# Toberemoved_Principal.net
KiCad netlist of a schematic drawn in Altium Designer
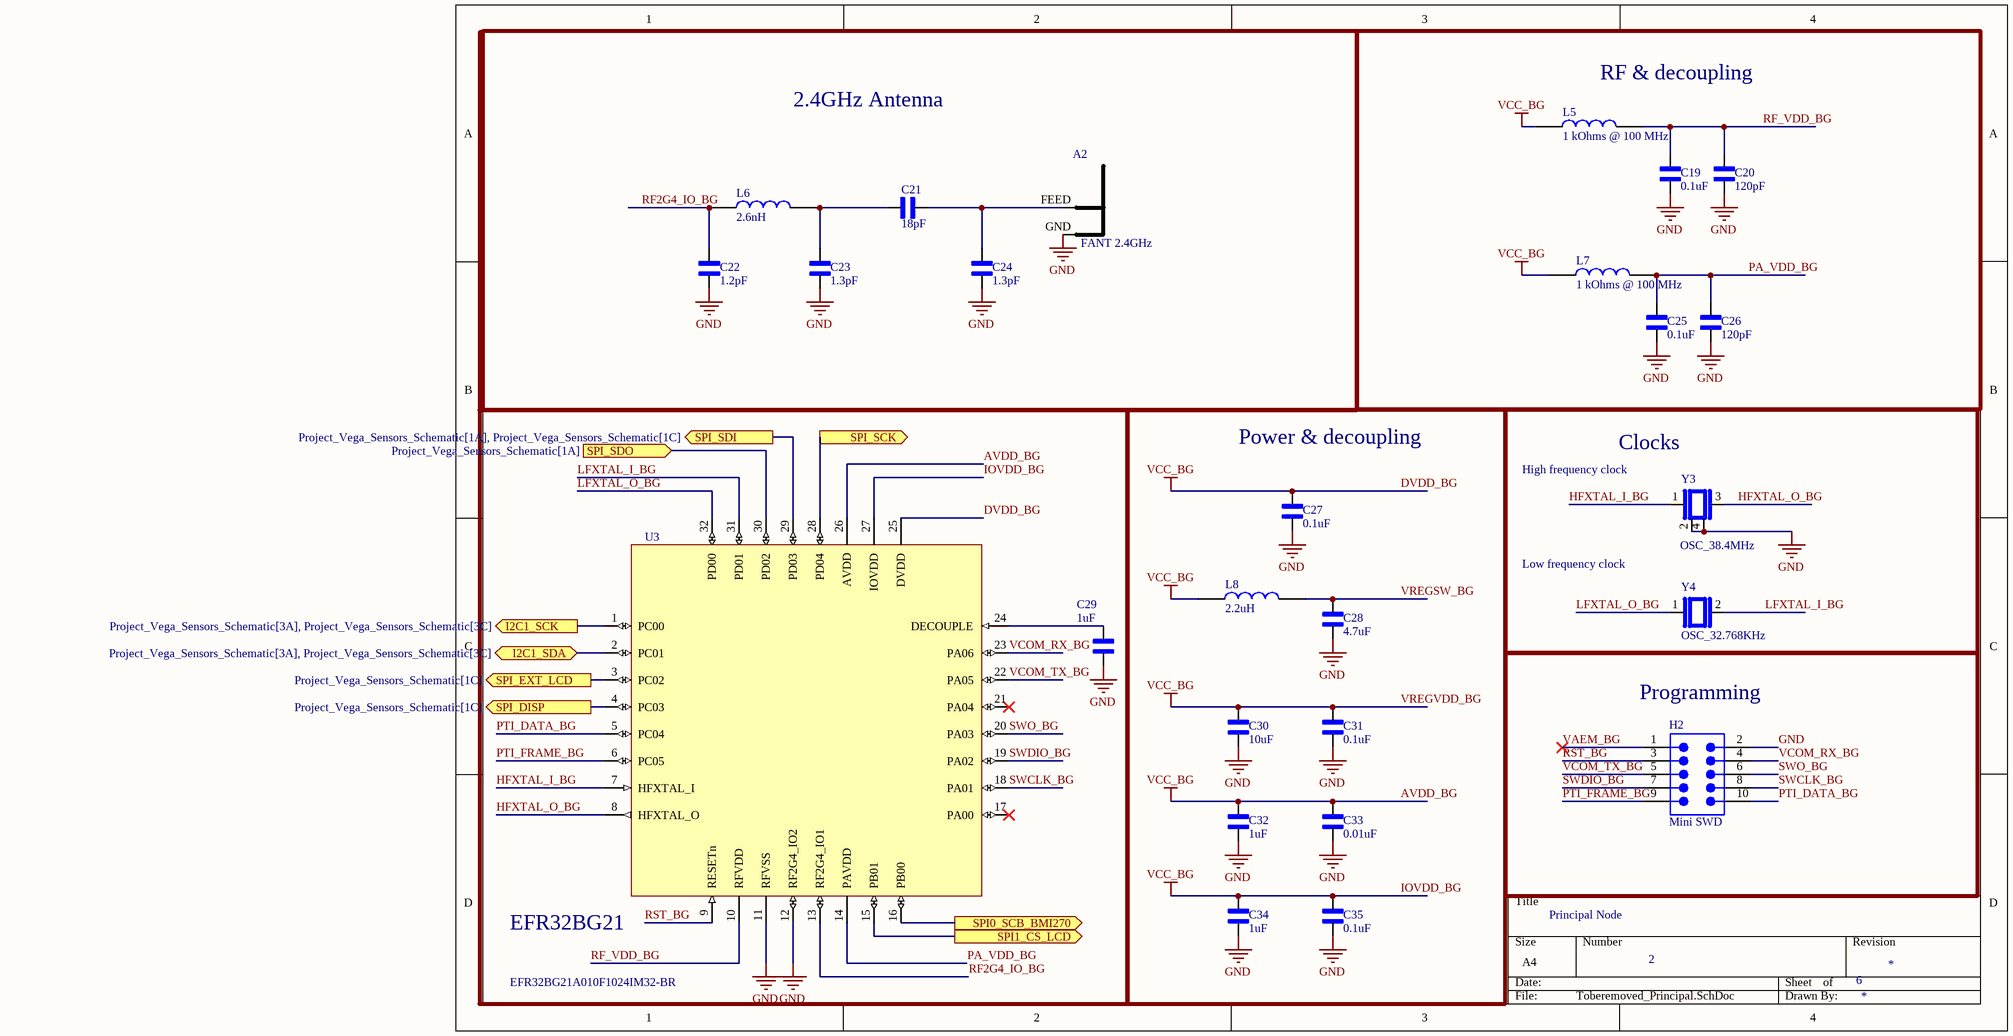
[diagram p0: Toberemoved_Principal.SchDoc]

(export (version "E")
  (design (tool "Eeschema 10.0.6"))
  (components
    (comp (ref "A2")
      (value "FANT 2.4GHz")
      (footprint "FANT_2P4")
      (description "Inverted F antenna")
      (libsource (lib "Project_Vega") (part "FANT_2P4"))
    )
    (comp (ref "C19")
      (value "0.1uF")
      (footprint "CAPC1608X90")
      (description "0.1 ÂµF Â±10% 50V Ceramic Capacitor X7R 0603 (1608 Metric)")
      (fields (field (name "MF") "Yageo") (field (name "MP") "CC0603KRX7R9BB104"))
      (libsource (lib "Project_Vega") (part "CC0603KRX7R9BB104"))
    )
    (comp (ref "C20")
      (value "120pF")
      (footprint "CAPC1608X90")
      (description "0.1 ÂµF Â±10% 50V Ceramic Capacitor X7R 0603 (1608 Metric)")
      (fields (field (name "MF") "Yageo") (field (name "MP") "CC0603KRX7R9BB104"))
      (libsource (lib "Project_Vega") (part "CC0603KRX7R9BB104"))
    )
    (comp (ref "C21")
      (value "18pF")
      (footprint "CAPC1608X90")
      (description "0.1 ÂµF Â±10% 50V Ceramic Capacitor X7R 0603 (1608 Metric)")
      (fields (field (name "MF") "Yageo") (field (name "MP") "CC0603KRX7R9BB104"))
      (libsource (lib "") (part "CC0603KRX7R9BB104_1"))
    )
    (comp (ref "C22")
      (value "1.2pF")
      (footprint "CAPC1608X90")
      (description "0.1 ÂµF Â±10% 50V Ceramic Capacitor X7R 0603 (1608 Metric)")
      (fields (field (name "MF") "Yageo") (field (name "MP") "CC0603KRX7R9BB104"))
      (libsource (lib "Project_Vega") (part "CC0603KRX7R9BB104"))
    )
    (comp (ref "C23")
      (value "1.3pF")
      (footprint "CAPC1608X90")
      (description "0.1 ÂµF Â±10% 50V Ceramic Capacitor X7R 0603 (1608 Metric)")
      (fields (field (name "MF") "Yageo") (field (name "MP") "CC0603KRX7R9BB104"))
      (libsource (lib "Project_Vega") (part "CC0603KRX7R9BB104"))
    )
    (comp (ref "C24")
      (value "1.3pF")
      (footprint "CAPC1608X90")
      (description "0.1 ÂµF Â±10% 50V Ceramic Capacitor X7R 0603 (1608 Metric)")
      (fields (field (name "MF") "Yageo") (field (name "MP") "CC0603KRX7R9BB104"))
      (libsource (lib "Project_Vega") (part "CC0603KRX7R9BB104"))
    )
    (comp (ref "C25")
      (value "0.1uF")
      (footprint "CAPC1608X90")
      (description "0.1 ÂµF Â±10% 50V Ceramic Capacitor X7R 0603 (1608 Metric)")
      (fields (field (name "MF") "Yageo") (field (name "MP") "CC0603KRX7R9BB104"))
      (libsource (lib "Project_Vega") (part "CC0603KRX7R9BB104"))
    )
    (comp (ref "C26")
      (value "120pF")
      (footprint "CAPC1608X90")
      (description "0.1 ÂµF Â±10% 50V Ceramic Capacitor X7R 0603 (1608 Metric)")
      (fields (field (name "MF") "Yageo") (field (name "MP") "CC0603KRX7R9BB104"))
      (libsource (lib "Project_Vega") (part "CC0603KRX7R9BB104"))
    )
    (comp (ref "C27")
      (value "0.1uF")
      (footprint "CAPC1608X90")
      (description "0.1 ÂµF Â±10% 50V Ceramic Capacitor X7R 0603 (1608 Metric)")
      (fields (field (name "MF") "Yageo") (field (name "MP") "CC0603KRX7R9BB104"))
      (libsource (lib "Project_Vega") (part "CC0603KRX7R9BB104"))
    )
    (comp (ref "C28")
      (value "4.7uF")
      (footprint "CAPC1608X90")
      (description "0.1 ÂµF Â±10% 50V Ceramic Capacitor X7R 0603 (1608 Metric)")
      (fields (field (name "MF") "Yageo") (field (name "MP") "CC0603KRX7R9BB104"))
      (libsource (lib "Project_Vega") (part "CC0603KRX7R9BB104"))
    )
    (comp (ref "C29")
      (value "1uF")
      (footprint "CAPC1608X90")
      (description "0.1 ÂµF Â±10% 50V Ceramic Capacitor X7R 0603 (1608 Metric)")
      (fields (field (name "MF") "Yageo") (field (name "MP") "CC0603KRX7R9BB104"))
      (libsource (lib "Project_Vega") (part "CC0603KRX7R9BB104"))
    )
    (comp (ref "C30")
      (value "10uF")
      (footprint "CAPC1608X90")
      (description "0.1 ÂµF Â±10% 50V Ceramic Capacitor X7R 0603 (1608 Metric)")
      (fields (field (name "MF") "Yageo") (field (name "MP") "CC0603KRX7R9BB104"))
      (libsource (lib "Project_Vega") (part "CC0603KRX7R9BB104"))
    )
    (comp (ref "C31")
      (value "0.1uF")
      (footprint "CAPC1608X90")
      (description "0.1 ÂµF Â±10% 50V Ceramic Capacitor X7R 0603 (1608 Metric)")
      (fields (field (name "MF") "Yageo") (field (name "MP") "CC0603KRX7R9BB104"))
      (libsource (lib "Project_Vega") (part "CC0603KRX7R9BB104"))
    )
    (comp (ref "C32")
      (value "1uF")
      (footprint "CAPC1608X90")
      (description "0.1 ÂµF Â±10% 50V Ceramic Capacitor X7R 0603 (1608 Metric)")
      (fields (field (name "MF") "Yageo") (field (name "MP") "CC0603KRX7R9BB104"))
      (libsource (lib "Project_Vega") (part "CC0603KRX7R9BB104"))
    )
    (comp (ref "C33")
      (value "0.01uF")
      (footprint "CAPC1608X90")
      (description "0.1 ÂµF Â±10% 50V Ceramic Capacitor X7R 0603 (1608 Metric)")
      (fields (field (name "MF") "Yageo") (field (name "MP") "CC0603KRX7R9BB104"))
      (libsource (lib "Project_Vega") (part "CC0603KRX7R9BB104"))
    )
    (comp (ref "C34")
      (value "1uF")
      (footprint "CAPC1608X90")
      (description "0.1 ÂµF Â±10% 50V Ceramic Capacitor X7R 0603 (1608 Metric)")
      (fields (field (name "MF") "Yageo") (field (name "MP") "CC0603KRX7R9BB104"))
      (libsource (lib "Project_Vega") (part "CC0603KRX7R9BB104"))
    )
    (comp (ref "C35")
      (value "0.1uF")
      (footprint "CAPC1608X90")
      (description "0.1 ÂµF Â±10% 50V Ceramic Capacitor X7R 0603 (1608 Metric)")
      (fields (field (name "MF") "Yageo") (field (name "MP") "CC0603KRX7R9BB104"))
      (libsource (lib "Project_Vega") (part "CC0603KRX7R9BB104"))
    )
    (comp (ref "H2")
      (value "Mini SWD")
      (footprint "FTSH-105-01-XXX-DV-K")
      (description "Mini SWD 0.05\" Pitch Connector - 10 Pin SMT Box Header")
      (fields
        (field (name "MANUFACTURER") "Adafruit Industries")
        (field (name "MANUFACTURER PART NUMBER") "4048")
      )
      (libsource (lib "Connectors") (part "Debug Connector Mini SWD - 0.05{dblquote}"))
    )
    (comp (ref "L5")
      (value "1 kOhms @ 100 MHz")
      (footprint "INDC1608X95N")
      (description "Inductor with Inductance 10uH Tol.+/-20% Package 0603 (1608)")
      (fields (field (name "MP") "LQM18DN100M70L") (field (name "MF") "Murata Electronics"))
      (libsource (lib "Project_Vega") (part "LQM18DN100M70L"))
    )
    (comp (ref "L6")
      (value "2.6nH")
      (footprint "INDC1608X95N")
      (description "Inductor with Inductance 10uH Tol.+/-20% Package 0603 (1608)")
      (fields (field (name "MP") "LQM18DN100M70L") (field (name "MF") "Murata Electronics"))
      (libsource (lib "Project_Vega") (part "LQM18DN100M70L"))
    )
    (comp (ref "L7")
      (value "1 kOhms @ 100 MHz")
      (footprint "INDC1608X95N")
      (description "Inductor with Inductance 10uH Tol.+/-20% Package 0603 (1608)")
      (fields (field (name "MP") "LQM18DN100M70L") (field (name "MF") "Murata Electronics"))
      (libsource (lib "Project_Vega") (part "LQM18DN100M70L"))
    )
    (comp (ref "L8")
      (value "2.2uH")
      (footprint "INDC1608X95N")
      (description "Inductor with Inductance 10uH Tol.+/-20% Package 0603 (1608)")
      (fields (field (name "MP") "LQM18DN100M70L") (field (name "MF") "Murata Electronics"))
      (libsource (lib "Project_Vega") (part "LQM18DN100M70L"))
    )
    (comp (ref "U3")
      (value "EFR32BG21A010F1024IM32-BR")
      (footprint "QFN32-EFR32xG2xIM32-BR")
      (description "Blue Gecko, QFN32, 2.4G, 10dB, Bluetooth 5.1, 1024kB, 96kB(RAM), 20 GPIO")
      (fields (field (name "MANUFACTURER") "Silicon Labs"))
      (libsource (lib "Project_Vega") (part "EFR32BG21A010F1024IM32-BR"))
    )
    (comp (ref "Y3")
      (value "OSC_38.4MHz")
      (footprint "OSC_38.4MHz")
      (description "38.4 MHz ±10ppm Crystal 10pF 40 Ohms 4-SMD, No Lead")
      (fields
        (field (name "MF") "{'manufacturer': u'Murata Electronics'}")
        (field (name "MP") "XRCGB38M400F2P00R0")
      )
      (libsource (lib "Project_Vega") (part "OSC_38.4MHz"))
    )
    (comp (ref "Y4")
      (value "OSC_32.768KHz")
      (footprint "OSC_32.768KHz")
      (description "Tuning Fork Crystal 32.768kHz in 1.2 x 2.0mm package")
      (fields (field (name "MF") "Micro Crystal") (field (name "MP") "CM8V-T1A-32.768KHZ-7PF-20PPM-TA-QC"))
      (libsource (lib "Project_Vega") (part "OSC_32.768KHz"))
    )
  )
  (nets
    (net (code "1") (name "/HFXTAL_I_BG") (class "Default")
      (node (ref "U3") (pin "7") (pinfunction "HFXTAL_I_7") (pintype "input"))
      (node (ref "Y3") (pin "1") (pinfunction "1_1") (pintype "passive"))
    )
    (net (code "2") (name "/HFXTAL_O_BG") (class "Default")
      (node (ref "U3") (pin "8") (pinfunction "HFXTAL_O_8") (pintype "output"))
      (node (ref "Y3") (pin "3") (pinfunction "3_3") (pintype "passive"))
    )
    (net (code "3") (name "/I2C1_SCK") (class "Default")
      (node (ref "U3") (pin "1") (pinfunction "PC00_1") (pintype "bidirectional"))
    )
    (net (code "4") (name "/I2C1_SDA") (class "Default")
      (node (ref "U3") (pin "2") (pinfunction "PC01_2") (pintype "bidirectional"))
    )
    (net (code "5") (name "/LFXTAL_I_BG") (class "Default")
      (node (ref "U3") (pin "31") (pinfunction "PD01_31") (pintype "bidirectional"))
      (node (ref "Y4") (pin "2") (pinfunction "2_2") (pintype "passive"))
    )
    (net (code "6") (name "/LFXTAL_O_BG") (class "Default")
      (node (ref "U3") (pin "32") (pinfunction "PD00_32") (pintype "bidirectional"))
      (node (ref "Y4") (pin "1") (pinfunction "1_1") (pintype "passive"))
    )
    (net (code "7") (name "/PA_VDD_BG") (class "Default")
      (node (ref "C25") (pin "1") (pinfunction "1_1") (pintype "passive"))
      (node (ref "C26") (pin "1") (pinfunction "1_1") (pintype "passive"))
      (node (ref "L7") (pin "2") (pinfunction "2_2") (pintype "passive"))
      (node (ref "U3") (pin "14") (pinfunction "PAVDD_14") (pintype "power_in"))
    )
    (net (code "8") (name "/PTI_DATA_BG") (class "Default")
      (node (ref "H2") (pin "10") (pinfunction "10_10") (pintype "passive"))
      (node (ref "U3") (pin "5") (pinfunction "PC04_5") (pintype "bidirectional"))
    )
    (net (code "9") (name "/PTI_FRAME_BG") (class "Default")
      (node (ref "H2") (pin "9") (pinfunction "9_9") (pintype "passive"))
      (node (ref "U3") (pin "6") (pinfunction "PC05_6") (pintype "bidirectional"))
    )
    (net (code "10") (name "/RF2G4_IO_BG") (class "Default")
      (node (ref "C22") (pin "1") (pinfunction "1_1") (pintype "passive"))
      (node (ref "L6") (pin "1") (pinfunction "1_1") (pintype "passive"))
      (node (ref "U3") (pin "13") (pinfunction "RF2G4_IO1_13") (pintype "bidirectional"))
    )
    (net (code "11") (name "/RF_VDD_BG") (class "Default")
      (node (ref "C19") (pin "1") (pinfunction "1_1") (pintype "passive"))
      (node (ref "C20") (pin "1") (pinfunction "1_1") (pintype "passive"))
      (node (ref "L5") (pin "2") (pinfunction "2_2") (pintype "passive"))
      (node (ref "U3") (pin "10") (pinfunction "RFVDD_10") (pintype "power_in"))
    )
    (net (code "12") (name "/RST_BG") (class "Default")
      (node (ref "H2") (pin "3") (pinfunction "3_3") (pintype "passive"))
      (node (ref "U3") (pin "9") (pinfunction "RESETn_9") (pintype "input"))
    )
    (net (code "13") (name "/SPI0_SCB_BMI270") (class "Default")
      (node (ref "U3") (pin "16") (pinfunction "PB00_16") (pintype "bidirectional"))
    )
    (net (code "14") (name "/SPI1_CS_LCD") (class "Default")
      (node (ref "U3") (pin "15") (pinfunction "PB01_15") (pintype "bidirectional"))
    )
    (net (code "15") (name "/SPI_DISP") (class "Default")
      (node (ref "U3") (pin "4") (pinfunction "PC03_4") (pintype "bidirectional"))
    )
    (net (code "16") (name "/SPI_EXT_LCD") (class "Default")
      (node (ref "U3") (pin "3") (pinfunction "PC02_3") (pintype "bidirectional"))
    )
    (net (code "17") (name "/SPI_SCK") (class "Default")
      (node (ref "U3") (pin "28") (pinfunction "PD04_28") (pintype "bidirectional"))
    )
    (net (code "18") (name "/SPI_SDI") (class "Default")
      (node (ref "U3") (pin "29") (pinfunction "PD03_29") (pintype "bidirectional"))
    )
    (net (code "19") (name "/SPI_SDO") (class "Default")
      (node (ref "U3") (pin "30") (pinfunction "PD02_30") (pintype "bidirectional"))
    )
    (net (code "20") (name "/SWCLK_BG") (class "Default")
      (node (ref "H2") (pin "8") (pinfunction "8_8") (pintype "passive"))
      (node (ref "U3") (pin "18") (pinfunction "PA01_18") (pintype "bidirectional"))
    )
    (net (code "21") (name "/SWDIO_BG") (class "Default")
      (node (ref "H2") (pin "7") (pinfunction "7_7") (pintype "passive"))
      (node (ref "U3") (pin "19") (pinfunction "PA02_19") (pintype "bidirectional"))
    )
    (net (code "22") (name "/SWO_BG") (class "Default")
      (node (ref "H2") (pin "6") (pinfunction "6_6") (pintype "passive"))
      (node (ref "U3") (pin "20") (pinfunction "PA03_20") (pintype "bidirectional"))
    )
    (net (code "23") (name "/VAEM_BG") (class "Default")
      (node (ref "H2") (pin "1") (pinfunction "1_1") (pintype "passive+no_connect"))
    )
    (net (code "24") (name "/VCOM_RX_BG") (class "Default")
      (node (ref "H2") (pin "4") (pinfunction "4_4") (pintype "passive"))
      (node (ref "U3") (pin "23") (pinfunction "PA06_23") (pintype "bidirectional"))
    )
    (net (code "25") (name "/VCOM_TX_BG") (class "Default")
      (node (ref "H2") (pin "5") (pinfunction "5_5") (pintype "passive"))
      (node (ref "U3") (pin "22") (pinfunction "PA05_22") (pintype "bidirectional"))
    )
    (net (code "26") (name "/VREGSW_BG") (class "Default")
      (node (ref "C28") (pin "1") (pinfunction "1_1") (pintype "passive"))
      (node (ref "L8") (pin "2") (pinfunction "2_2") (pintype "passive"))
    )
    (net (code "27") (name "GND") (class "Default")
      (node (ref "A2") (pin "GND") (pinfunction "6_GND") (pintype "passive"))
      (node (ref "C19") (pin "2") (pinfunction "2_2") (pintype "passive"))
      (node (ref "C20") (pin "2") (pinfunction "2_2") (pintype "passive"))
      (node (ref "C22") (pin "2") (pinfunction "2_2") (pintype "passive"))
      (node (ref "C23") (pin "2") (pinfunction "2_2") (pintype "passive"))
      (node (ref "C24") (pin "2") (pinfunction "2_2") (pintype "passive"))
      (node (ref "C25") (pin "2") (pinfunction "2_2") (pintype "passive"))
      (node (ref "C26") (pin "2") (pinfunction "2_2") (pintype "passive"))
      (node (ref "C27") (pin "2") (pinfunction "2_2") (pintype "passive"))
      (node (ref "C28") (pin "2") (pinfunction "2_2") (pintype "passive"))
      (node (ref "C29") (pin "2") (pinfunction "2_2") (pintype "passive"))
      (node (ref "C30") (pin "2") (pinfunction "2_2") (pintype "passive"))
      (node (ref "C31") (pin "2") (pinfunction "2_2") (pintype "passive"))
      (node (ref "C32") (pin "2") (pinfunction "2_2") (pintype "passive"))
      (node (ref "C33") (pin "2") (pinfunction "2_2") (pintype "passive"))
      (node (ref "C34") (pin "2") (pinfunction "2_2") (pintype "passive"))
      (node (ref "C35") (pin "2") (pinfunction "2_2") (pintype "passive"))
      (node (ref "H2") (pin "2") (pinfunction "2_2") (pintype "passive"))
      (node (ref "U3") (pin "11") (pinfunction "RFVSS_11") (pintype "power_in"))
      (node (ref "U3") (pin "12") (pinfunction "RF2G4_IO2_12") (pintype "bidirectional"))
      (node (ref "Y3") (pin "2") (pinfunction "2_2") (pintype "passive"))
      (node (ref "Y3") (pin "4") (pinfunction "4_4") (pintype "passive"))
    )
    (net (code "28") (name "Net-(A2-6-PadFEED)") (class "Default")
      (node (ref "A2") (pin "FEED") (pinfunction "6_FEED") (pintype "passive"))
      (node (ref "C21") (pin "2") (pinfunction "2_2") (pintype "passive"))
      (node (ref "C24") (pin "1") (pinfunction "1_1") (pintype "passive"))
    )
    (net (code "29") (name "Net-(C21-Pad1)") (class "Default")
      (node (ref "C21") (pin "1") (pinfunction "1_1") (pintype "passive"))
      (node (ref "C23") (pin "1") (pinfunction "1_1") (pintype "passive"))
      (node (ref "L6") (pin "2") (pinfunction "2_2") (pintype "passive"))
    )
    (net (code "30") (name "Net-(U3-DECOUPLE)") (class "Default")
      (node (ref "C29") (pin "1") (pinfunction "1_1") (pintype "passive"))
      (node (ref "U3") (pin "24") (pinfunction "DECOUPLE_24") (pintype "input"))
    )
    (net (code "31") (name "VCC_BG") (class "Default")
      (node (ref "C27") (pin "1") (pinfunction "1_1") (pintype "passive"))
      (node (ref "C30") (pin "1") (pinfunction "1_1") (pintype "passive"))
      (node (ref "C31") (pin "1") (pinfunction "1_1") (pintype "passive"))
      (node (ref "C32") (pin "1") (pinfunction "1_1") (pintype "passive"))
      (node (ref "C33") (pin "1") (pinfunction "1_1") (pintype "passive"))
      (node (ref "C34") (pin "1") (pinfunction "1_1") (pintype "passive"))
      (node (ref "C35") (pin "1") (pinfunction "1_1") (pintype "passive"))
      (node (ref "L5") (pin "1") (pinfunction "1_1") (pintype "passive"))
      (node (ref "L7") (pin "1") (pinfunction "1_1") (pintype "passive"))
      (node (ref "L8") (pin "1") (pinfunction "1_1") (pintype "passive"))
      (node (ref "U3") (pin "25") (pinfunction "DVDD_25") (pintype "power_in"))
      (node (ref "U3") (pin "26") (pinfunction "AVDD_26") (pintype "power_in"))
      (node (ref "U3") (pin "27") (pinfunction "IOVDD_27") (pintype "power_in"))
    )
    (net (code "32") (name "unconnected-(U3-PA00-Pad17)") (class "Default")
      (node (ref "U3") (pin "17") (pinfunction "PA00_17") (pintype "bidirectional+no_connect"))
    )
    (net (code "33") (name "unconnected-(U3-PA04-Pad21)") (class "Default")
      (node (ref "U3") (pin "21") (pinfunction "PA04_21") (pintype "bidirectional+no_connect"))
    )
  )
)
